# WeatherStation_pcb.net
KiCad netlist of a schematic drawn in EAGLE
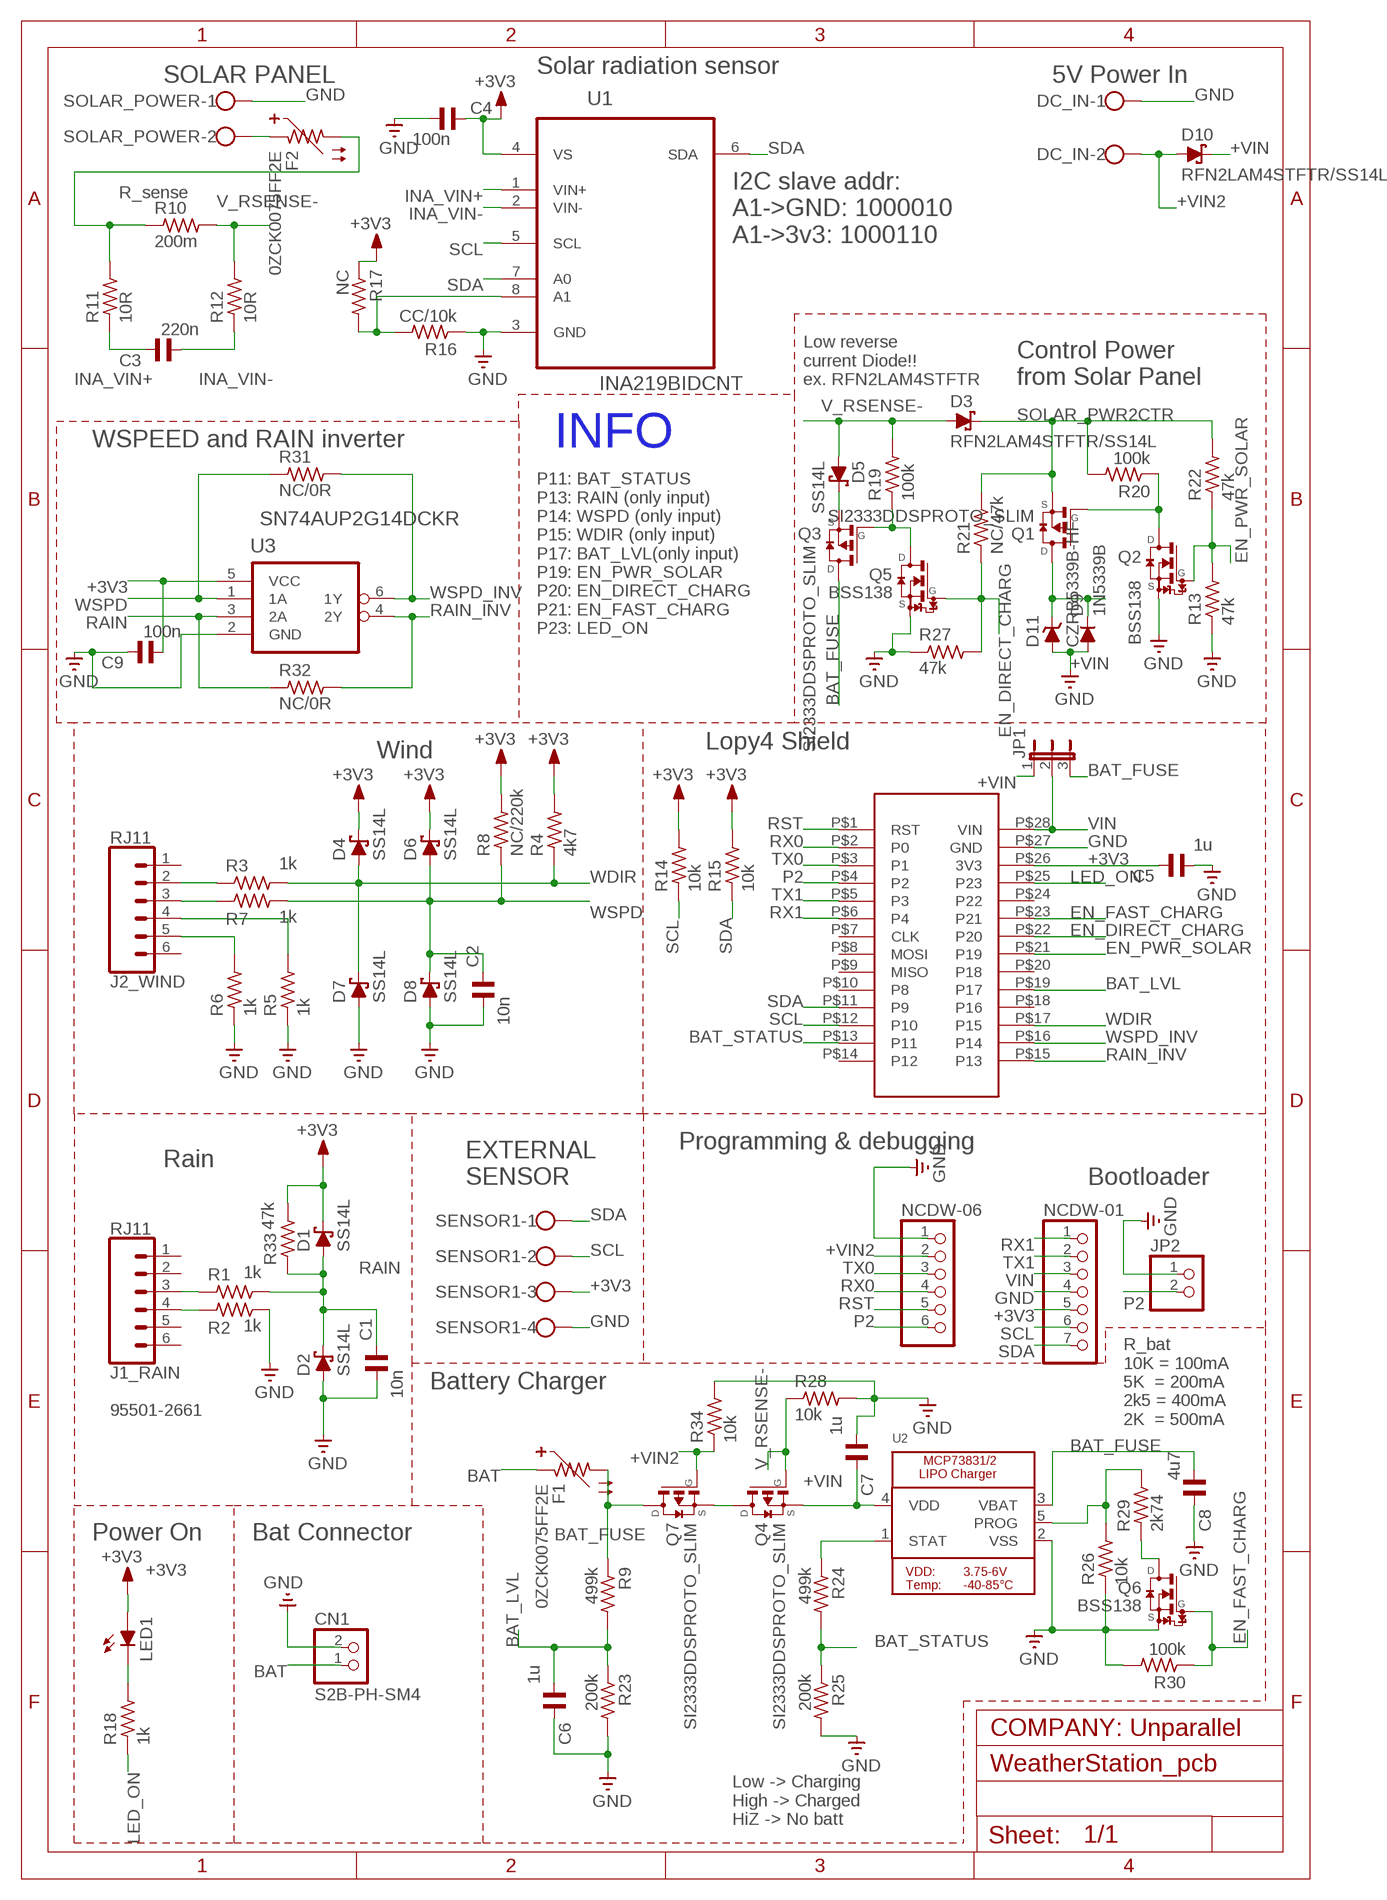
[diagram p0: schematic, sheet 1]

(export (version "E")
  (design (tool "Eeschema 10.0.6"))
  (components
    (comp (ref "C1")
      (value "10n")
      (footprint "eagle-import:C0603_C0805_PROTO_SLIM")
      (libsource (lib "eagle-import") (part "C-EUC0603/C0805_PROTO_SLIM"))
    )
    (comp (ref "C2")
      (value "10n")
      (footprint "eagle-import:C0603_C0805_PROTO_SLIM")
      (libsource (lib "eagle-import") (part "C-EUC0603/C0805_PROTO_SLIM"))
    )
    (comp (ref "C3")
      (value "220n")
      (footprint "eagle-import:C0603")
      (libsource (lib "eagle-import") (part "C-EUC0603"))
    )
    (comp (ref "C4")
      (value "100n")
      (footprint "eagle-import:C0603")
      (libsource (lib "eagle-import") (part "C-EUC0603"))
    )
    (comp (ref "C5")
      (value "1u")
      (footprint "eagle-import:C0603_C0805_PROTO_SLIM")
      (libsource (lib "eagle-import") (part "C-EUC0603/C0805_PROTO_SLIM"))
    )
    (comp (ref "C6")
      (value "1u")
      (footprint "eagle-import:C0603_C0805_PROTO_SLIM")
      (libsource (lib "eagle-import") (part "C-EUC0603/C0805_PROTO_SLIM"))
    )
    (comp (ref "C7")
      (value "1u")
      (footprint "eagle-import:C0603_C0805_PROTO_SLIM")
      (libsource (lib "eagle-import") (part "C-EUC0603/C0805_PROTO_SLIM"))
    )
    (comp (ref "C8")
      (value "4u7")
      (footprint "eagle-import:C0603_C0805_PROTO_SLIM")
      (libsource (lib "eagle-import") (part "C-EUC0603/C0805_PROTO_SLIM"))
    )
    (comp (ref "C9")
      (value "100n")
      (footprint "eagle-import:C0603")
      (libsource (lib "eagle-import") (part "C-EUC0603"))
    )
    (comp (ref "CN1")
      (value "S2B-PH-SM4")
      (footprint "eagle-import:JST-PH-2-SMT-RA")
      (libsource (lib "eagle-import") (part "JST_2PIN-SMT-RA"))
    )
    (comp (ref "D1")
      (value "SS14L")
      (footprint "eagle-import:SUB_SMA_PROTO")
      (libsource (lib "eagle-import") (part "SCHOTTKY-DIODESUB_SMA_PROTO"))
    )
    (comp (ref "D2")
      (value "SS14L")
      (footprint "eagle-import:SUB_SMA_PROTO")
      (libsource (lib "eagle-import") (part "SCHOTTKY-DIODESUB_SMA_PROTO"))
    )
    (comp (ref "D3")
      (value "RFN2LAM4STFTR/SS14L")
      (footprint "eagle-import:SMA_SOD-128_PROTO")
      (libsource (lib "eagle-import") (part "SCHOTTKY-DIODESMA_SOD-128_PROTO"))
    )
    (comp (ref "D4")
      (value "SS14L")
      (footprint "eagle-import:SUB_SMA_PROTO")
      (libsource (lib "eagle-import") (part "SCHOTTKY-DIODESUB_SMA_PROTO"))
    )
    (comp (ref "D5")
      (value "SS14L")
      (footprint "eagle-import:SUB_SMA_PROTO")
      (libsource (lib "eagle-import") (part "SCHOTTKY-DIODESUB_SMA_PROTO"))
    )
    (comp (ref "D6")
      (value "SS14L")
      (footprint "eagle-import:SUB_SMA_PROTO")
      (libsource (lib "eagle-import") (part "SCHOTTKY-DIODESUB_SMA_PROTO"))
    )
    (comp (ref "D7")
      (value "SS14L")
      (footprint "eagle-import:SUB_SMA_PROTO")
      (libsource (lib "eagle-import") (part "SCHOTTKY-DIODESUB_SMA_PROTO"))
    )
    (comp (ref "D8")
      (value "SS14L")
      (footprint "eagle-import:SUB_SMA_PROTO")
      (libsource (lib "eagle-import") (part "SCHOTTKY-DIODESUB_SMA_PROTO"))
    )
    (comp (ref "D9")
      (value "1N5339B")
      (footprint "eagle-import:DO15-12")
      (libsource (lib "eagle-import") (part "DIODE-DO15-12"))
    )
    (comp (ref "D10")
      (value "RFN2LAM4STFTR/SS14L")
      (footprint "eagle-import:SMA_SOD-128_PROTO")
      (libsource (lib "eagle-import") (part "SCHOTTKY-DIODESMA_SOD-128_PROTO"))
    )
    (comp (ref "D11")
      (value "CZRB5339B-HF")
      (footprint "eagle-import:SMB_PROTO")
      (libsource (lib "eagle-import") (part "ZENER-DIODE-PROTO"))
    )
    (comp (ref "DC_IN")
      (value "W237-102")
      (footprint "eagle-import:W237-102")
      (libsource (lib "eagle-import") (part "W237-102"))
    )
    (comp (ref "F1")
      (value "0ZCK0075FF2E")
      (footprint "eagle-import:R0603_R0805_PROTO_SLIM")
      (libsource (lib "eagle-import") (part "PTC-0603_0805_PROTO_SLIM"))
    )
    (comp (ref "F2")
      (value "0ZCK0075FF2E")
      (footprint "eagle-import:R0805")
      (libsource (lib "eagle-import") (part "PTC-0805"))
    )
    (comp (ref "J1_RAIN")
      (value "RJ11")
      (footprint "eagle-import:RJ11-6")
      (libsource (lib "eagle-import") (part "RJ11-6"))
    )
    (comp (ref "J2_WIND")
      (value "RJ11")
      (footprint "eagle-import:RJ11-6")
      (libsource (lib "eagle-import") (part "RJ11-6"))
    )
    (comp (ref "JP1")
      (value "JP2E-0805")
      (footprint "eagle-import:R0805_2")
      (libsource (lib "eagle-import") (part "JP2E-0805"))
    )
    (comp (ref "JP2")
      (value "PINHD-1X2")
      (footprint "eagle-import:1X02")
      (libsource (lib "eagle-import") (part "PINHD-1X2"))
    )
    (comp (ref "LED1")
      (value "LEDCHIP-LED0805")
      (footprint "eagle-import:CHIP-LED0805")
      (libsource (lib "eagle-import") (part "LEDCHIP-LED0805"))
    )
    (comp (ref "NCDW-01")
      (value "PINHD-1X7")
      (footprint "eagle-import:1X07")
      (libsource (lib "eagle-import") (part "PINHD-1X7"))
    )
    (comp (ref "NCDW-06")
      (value "PINHD-1X6")
      (footprint "eagle-import:1X06")
      (libsource (lib "eagle-import") (part "PINHD-1X6"))
    )
    (comp (ref "Q1")
      (value "SI2333DDSPROTO_SLIM")
      (footprint "eagle-import:SOT23_PROTO_SLIM")
      (libsource (lib "eagle-import") (part "SI2333DDSPROTO_SLIM"))
    )
    (comp (ref "Q2")
      (value "BSS138")
      (footprint "eagle-import:SOT23_PROTO_SLIM")
      (libsource (lib "eagle-import") (part "NX7002AKPROTO_SLIM"))
    )
    (comp (ref "Q3")
      (value "SI2333DDSPROTO_SLIM")
      (footprint "eagle-import:SOT23_PROTO_SLIM")
      (libsource (lib "eagle-import") (part "SI2333DDSPROTO_SLIM"))
    )
    (comp (ref "Q4")
      (value "SI2333DDSPROTO_SLIM")
      (footprint "eagle-import:SOT23_PROTO_SLIM")
      (libsource (lib "eagle-import") (part "SI2333DDSPROTO_SLIM"))
    )
    (comp (ref "Q5")
      (value "BSS138")
      (footprint "eagle-import:SOT23_PROTO_SLIM")
      (libsource (lib "eagle-import") (part "NX7002AKPROTO_SLIM"))
    )
    (comp (ref "Q6")
      (value "BSS138")
      (footprint "eagle-import:SOT23_PROTO_SLIM")
      (libsource (lib "eagle-import") (part "NX7002AKPROTO_SLIM"))
    )
    (comp (ref "Q7")
      (value "SI2333DDSPROTO_SLIM")
      (footprint "eagle-import:SOT23_PROTO_SLIM")
      (libsource (lib "eagle-import") (part "SI2333DDSPROTO_SLIM"))
    )
    (comp (ref "R1")
      (value "1k")
      (footprint "eagle-import:R0603")
      (libsource (lib "eagle-import") (part "R-EU_R0603"))
    )
    (comp (ref "R2")
      (value "1k")
      (footprint "eagle-import:R0603")
      (libsource (lib "eagle-import") (part "R-EU_R0603"))
    )
    (comp (ref "R3")
      (value "1k")
      (footprint "eagle-import:R0603")
      (libsource (lib "eagle-import") (part "R-EU_R0603"))
    )
    (comp (ref "R4")
      (value "4k7")
      (footprint "eagle-import:R0603_R0805_PROTO_SLIM")
      (libsource (lib "eagle-import") (part "R-EU_R0603/R0805_PROTO_SLIM"))
    )
    (comp (ref "R5")
      (value "1k")
      (footprint "eagle-import:R0603")
      (libsource (lib "eagle-import") (part "R-EU_R0603"))
    )
    (comp (ref "R6")
      (value "1k")
      (footprint "eagle-import:R0603")
      (libsource (lib "eagle-import") (part "R-EU_R0603"))
    )
    (comp (ref "R7")
      (value "1k")
      (footprint "eagle-import:R0603")
      (libsource (lib "eagle-import") (part "R-EU_R0603"))
    )
    (comp (ref "R8")
      (value "NC/220k")
      (footprint "eagle-import:R0603_R0805_PROTO_SLIM")
      (libsource (lib "eagle-import") (part "R-EU_R0603/R0805_PROTO_SLIM"))
    )
    (comp (ref "R9")
      (value "499k")
      (footprint "eagle-import:R0603_R0805_PROTO_SLIM")
      (libsource (lib "eagle-import") (part "R-EU_R0603/R0805_PROTO_SLIM"))
    )
    (comp (ref "R10")
      (value "200m")
      (footprint "eagle-import:R0603_R0805_PROTO_SLIM")
      (libsource (lib "eagle-import") (part "R-EU_R0603/R0805_PROTO_SLIM"))
    )
    (comp (ref "R11")
      (value "10R")
      (footprint "eagle-import:R0603")
      (libsource (lib "eagle-import") (part "R-EU_R0603"))
    )
    (comp (ref "R12")
      (value "10R")
      (footprint "eagle-import:R0603")
      (libsource (lib "eagle-import") (part "R-EU_R0603"))
    )
    (comp (ref "R13")
      (value "47k")
      (footprint "eagle-import:R0603")
      (libsource (lib "eagle-import") (part "R-EU_R0603"))
    )
    (comp (ref "R14")
      (value "10k")
      (footprint "eagle-import:R0603")
      (libsource (lib "eagle-import") (part "R-EU_R0603"))
    )
    (comp (ref "R15")
      (value "10k")
      (footprint "eagle-import:R0603")
      (libsource (lib "eagle-import") (part "R-EU_R0603"))
    )
    (comp (ref "R16")
      (value "CC/10k")
      (footprint "eagle-import:R0603")
      (libsource (lib "eagle-import") (part "R-EU_R0603"))
    )
    (comp (ref "R17")
      (value "NC")
      (footprint "eagle-import:R0603")
      (libsource (lib "eagle-import") (part "R-EU_R0603"))
    )
    (comp (ref "R18")
      (value "1k")
      (footprint "eagle-import:R0603")
      (libsource (lib "eagle-import") (part "R-EU_R0603"))
    )
    (comp (ref "R19")
      (value "100k")
      (footprint "eagle-import:R0603")
      (libsource (lib "eagle-import") (part "R-EU_R0603"))
    )
    (comp (ref "R20")
      (value "100k")
      (footprint "eagle-import:R0603")
      (libsource (lib "eagle-import") (part "R-EU_R0603"))
    )
    (comp (ref "R21")
      (value "NC/47k")
      (footprint "eagle-import:R0603")
      (libsource (lib "eagle-import") (part "R-EU_R0603"))
    )
    (comp (ref "R22")
      (value "47k")
      (footprint "eagle-import:R0603")
      (libsource (lib "eagle-import") (part "R-EU_R0603"))
    )
    (comp (ref "R23")
      (value "200k")
      (footprint "eagle-import:R0603_R0805_PROTO_SLIM")
      (libsource (lib "eagle-import") (part "R-EU_R0603/R0805_PROTO_SLIM"))
    )
    (comp (ref "R24")
      (value "499k")
      (footprint "eagle-import:R0603_R0805_PROTO_SLIM")
      (libsource (lib "eagle-import") (part "R-EU_R0603/R0805_PROTO_SLIM"))
    )
    (comp (ref "R25")
      (value "200k")
      (footprint "eagle-import:R0603_R0805_PROTO_SLIM")
      (libsource (lib "eagle-import") (part "R-EU_R0603/R0805_PROTO_SLIM"))
    )
    (comp (ref "R26")
      (value "10k")
      (footprint "eagle-import:R0603_R0805_PROTO_SLIM")
      (libsource (lib "eagle-import") (part "R-EU_R0603/R0805_PROTO_SLIM"))
    )
    (comp (ref "R27")
      (value "47k")
      (footprint "eagle-import:R0603")
      (libsource (lib "eagle-import") (part "R-EU_R0603"))
    )
    (comp (ref "R28")
      (value "10k")
      (footprint "eagle-import:R0603")
      (libsource (lib "eagle-import") (part "R-EU_R0603"))
    )
    (comp (ref "R29")
      (value "2k74")
      (footprint "eagle-import:R0603_R0805_PROTO_SLIM")
      (libsource (lib "eagle-import") (part "R-EU_R0603/R0805_PROTO_SLIM"))
    )
    (comp (ref "R30")
      (value "100k")
      (footprint "eagle-import:R0603_R0805_PROTO_SLIM")
      (libsource (lib "eagle-import") (part "R-EU_R0603/R0805_PROTO_SLIM"))
    )
    (comp (ref "R31")
      (value "NC/0R")
      (footprint "eagle-import:R0603_R0805_PROTO_SLIM")
      (libsource (lib "eagle-import") (part "R-EU_R0603/R0805_PROTO_SLIM"))
    )
    (comp (ref "R32")
      (value "NC/0R")
      (footprint "eagle-import:R0603_R0805_PROTO_SLIM")
      (libsource (lib "eagle-import") (part "R-EU_R0603/R0805_PROTO_SLIM"))
    )
    (comp (ref "R33")
      (value "47k")
      (footprint "eagle-import:R0603")
      (libsource (lib "eagle-import") (part "R-EU_R0603"))
    )
    (comp (ref "R34")
      (value "10k")
      (footprint "eagle-import:R0603")
      (libsource (lib "eagle-import") (part "R-EU_R0603"))
    )
    (comp (ref "SENSOR1")
      (value "W237-4")
      (footprint "eagle-import:W237-4")
      (libsource (lib "eagle-import") (part "W237-4"))
    )
    (comp (ref "SOLAR_POWER")
      (value "W237-102")
      (footprint "eagle-import:W237-102")
      (libsource (lib "eagle-import") (part "W237-102"))
    )
    (comp (ref "U$2")
      (value "LOPY4_SHIELD")
      (footprint "eagle-import:LOPY4_SHIELD")
      (libsource (lib "eagle-import") (part "LOPY4_SHIELD"))
    )
    (comp (ref "U1")
      (value "INA219BIDCNT")
      (footprint "eagle-import:SOT65P280X145-8N")
      (libsource (lib "eagle-import") (part "INA219BIDCNT"))
    )
    (comp (ref "U2")
      (value "MCP73831/2")
      (footprint "eagle-import:SOT23-5")
      (libsource (lib "eagle-import") (part "MCP73831/2"))
    )
    (comp (ref "U3")
      (value "SN74AUP2G14DCKR")
      (footprint "eagle-import:SOT65P210X110-6N_EDIT")
      (libsource (lib "eagle-import") (part "SN74AUP2G14-DCKR"))
    )
  )
  (nets
    (net (code "1") (name "+3V3") (class "Default")
      (node (ref "C4") (pin "1") (pinfunction "1_1") (pintype "passive"))
      (node (ref "C5") (pin "1") (pinfunction "1_1") (pintype "passive"))
      (node (ref "C9") (pin "2") (pinfunction "2_2") (pintype "passive"))
      (node (ref "D1") (pin "C") (pinfunction "C_C") (pintype "passive"))
      (node (ref "D4") (pin "C") (pinfunction "C_C") (pintype "passive"))
      (node (ref "D6") (pin "C") (pinfunction "C_C") (pintype "passive"))
      (node (ref "LED1") (pin "A") (pinfunction "A_A") (pintype "passive"))
      (node (ref "NCDW-01") (pin "5") (pinfunction "5_5") (pintype "passive"))
      (node (ref "R14") (pin "2") (pinfunction "2_2") (pintype "passive"))
      (node (ref "R15") (pin "2") (pinfunction "2_2") (pintype "passive"))
      (node (ref "R17") (pin "1") (pinfunction "1_1") (pintype "passive"))
      (node (ref "R33") (pin "2") (pinfunction "2_2") (pintype "passive"))
      (node (ref "R4") (pin "2") (pinfunction "2_2") (pintype "passive"))
      (node (ref "R8") (pin "2") (pinfunction "2_2") (pintype "passive"))
      (node (ref "SENSOR1") (pin "3") (pinfunction "KL_3") (pintype "passive"))
      (node (ref "U$2") (pin "P$26") (pinfunction "3V3_P$26") (pintype "power_in"))
      (node (ref "U1") (pin "4") (pinfunction "VS_4") (pintype "power_in"))
      (node (ref "U3") (pin "5") (pinfunction "VCC_5") (pintype "power_in"))
    )
    (net (code "2") (name "/+VIN") (class "Default")
      (node (ref "C7") (pin "1") (pinfunction "1_1") (pintype "passive"))
      (node (ref "D10") (pin "C") (pinfunction "C_C") (pintype "passive"))
      (node (ref "D11") (pin "C") (pinfunction "C_C") (pintype "passive"))
      (node (ref "D9") (pin "C") (pinfunction "C_C") (pintype "passive"))
      (node (ref "JP1") (pin "1") (pinfunction "1_1") (pintype "passive"))
      (node (ref "Q1") (pin "3") (pinfunction "D_3") (pintype "passive"))
      (node (ref "Q4") (pin "2") (pinfunction "S_2") (pintype "passive"))
      (node (ref "U2") (pin "4") (pinfunction "VDD_4") (pintype "power_in"))
    )
    (net (code "3") (name "/+VIN2") (class "Default")
      (node (ref "D10") (pin "A") (pinfunction "A_A") (pintype "passive"))
      (node (ref "DC_IN") (pin "2") (pinfunction "KL_2") (pintype "passive"))
      (node (ref "NCDW-06") (pin "2") (pinfunction "2_2") (pintype "passive"))
      (node (ref "Q7") (pin "1") (pinfunction "G_1") (pintype "passive"))
      (node (ref "R34") (pin "1") (pinfunction "1_1") (pintype "passive"))
    )
    (net (code "4") (name "/BAT") (class "Default")
      (node (ref "CN1") (pin "1") (pinfunction "2_1") (pintype "passive"))
      (node (ref "F1") (pin "1") (pinfunction "1_1") (pintype "passive"))
    )
    (net (code "5") (name "/BAT_FUSE") (class "Default")
      (node (ref "C8") (pin "2") (pinfunction "2_2") (pintype "passive"))
      (node (ref "F1") (pin "2") (pinfunction "2_2") (pintype "passive"))
      (node (ref "JP1") (pin "3") (pinfunction "3_3") (pintype "passive"))
      (node (ref "Q3") (pin "3") (pinfunction "D_3") (pintype "passive"))
      (node (ref "Q7") (pin "3") (pinfunction "D_3") (pintype "passive"))
      (node (ref "R9") (pin "1") (pinfunction "1_1") (pintype "passive"))
      (node (ref "U2") (pin "3") (pinfunction "VBAT_3") (pintype "power_in"))
    )
    (net (code "6") (name "/BAT_LVL") (class "Default")
      (node (ref "C6") (pin "2") (pinfunction "2_2") (pintype "passive"))
      (node (ref "R23") (pin "1") (pinfunction "1_1") (pintype "passive"))
      (node (ref "R9") (pin "2") (pinfunction "2_2") (pintype "passive"))
      (node (ref "U$2") (pin "P$19") (pinfunction "P17_P$19") (pintype "bidirectional"))
    )
    (net (code "7") (name "/BAT_STATUS") (class "Default")
      (node (ref "R24") (pin "2") (pinfunction "2_2") (pintype "passive"))
      (node (ref "R25") (pin "1") (pinfunction "1_1") (pintype "passive"))
      (node (ref "U$2") (pin "P$13") (pinfunction "P11_P$13") (pintype "bidirectional"))
    )
    (net (code "8") (name "/EN_DIRECT_CHARG") (class "Default")
      (node (ref "Q5") (pin "1") (pinfunction "G_1") (pintype "passive"))
      (node (ref "R21") (pin "1") (pinfunction "1_1") (pintype "passive"))
      (node (ref "R27") (pin "2") (pinfunction "2_2") (pintype "passive"))
      (node (ref "U$2") (pin "P$22") (pinfunction "P20_P$22") (pintype "bidirectional"))
    )
    (net (code "9") (name "/EN_FAST_CHARG") (class "Default")
      (node (ref "Q6") (pin "1") (pinfunction "G_1") (pintype "passive"))
      (node (ref "R30") (pin "1") (pinfunction "1_1") (pintype "passive"))
      (node (ref "U$2") (pin "P$23") (pinfunction "P21_P$23") (pintype "bidirectional"))
    )
    (net (code "10") (name "/EN_PWR_SOLAR") (class "Default")
      (node (ref "Q2") (pin "1") (pinfunction "G_1") (pintype "passive"))
      (node (ref "R13") (pin "2") (pinfunction "2_2") (pintype "passive"))
      (node (ref "R22") (pin "1") (pinfunction "1_1") (pintype "passive"))
      (node (ref "U$2") (pin "P$21") (pinfunction "P19_P$21") (pintype "bidirectional"))
    )
    (net (code "11") (name "/INA_VIN+") (class "Default")
      (node (ref "C3") (pin "1") (pinfunction "1_1") (pintype "passive"))
      (node (ref "R11") (pin "1") (pinfunction "1_1") (pintype "passive"))
      (node (ref "U1") (pin "1") (pinfunction "VIN+_1") (pintype "power_in"))
    )
    (net (code "12") (name "/INA_VIN-") (class "Default")
      (node (ref "C3") (pin "2") (pinfunction "2_2") (pintype "passive"))
      (node (ref "R12") (pin "1") (pinfunction "1_1") (pintype "passive"))
      (node (ref "U1") (pin "2") (pinfunction "VIN-_2") (pintype "power_in"))
    )
    (net (code "13") (name "/LED_ON") (class "Default")
      (node (ref "R18") (pin "1") (pinfunction "1_1") (pintype "passive"))
      (node (ref "U$2") (pin "P$25") (pinfunction "P23_P$25") (pintype "bidirectional"))
    )
    (net (code "14") (name "/P2") (class "Default")
      (node (ref "JP2") (pin "2") (pinfunction "2_2") (pintype "passive"))
      (node (ref "NCDW-06") (pin "6") (pinfunction "6_6") (pintype "passive"))
      (node (ref "U$2") (pin "P$4") (pinfunction "P2_P$4") (pintype "bidirectional"))
    )
    (net (code "15") (name "/RAIN") (class "Default")
      (node (ref "C1") (pin "1") (pinfunction "1_1") (pintype "passive"))
      (node (ref "D1") (pin "A") (pinfunction "A_A") (pintype "passive"))
      (node (ref "D2") (pin "C") (pinfunction "C_C") (pintype "passive"))
      (node (ref "R1") (pin "2") (pinfunction "2_2") (pintype "passive"))
      (node (ref "R32") (pin "1") (pinfunction "1_1") (pintype "passive"))
      (node (ref "R33") (pin "1") (pinfunction "1_1") (pintype "passive"))
      (node (ref "U3") (pin "3") (pinfunction "2A_3") (pintype "input"))
    )
    (net (code "16") (name "/RAIN_INV") (class "Default")
      (node (ref "R32") (pin "2") (pinfunction "2_2") (pintype "passive"))
      (node (ref "U$2") (pin "P$15") (pinfunction "P13_P$15") (pintype "bidirectional"))
      (node (ref "U3") (pin "4") (pinfunction "2Y_4") (pintype "output"))
    )
    (net (code "17") (name "/RST") (class "Default")
      (node (ref "NCDW-06") (pin "5") (pinfunction "5_5") (pintype "passive"))
      (node (ref "U$2") (pin "P$1") (pinfunction "RST_P$1") (pintype "input"))
    )
    (net (code "18") (name "/RX0") (class "Default")
      (node (ref "NCDW-06") (pin "4") (pinfunction "4_4") (pintype "passive"))
      (node (ref "U$2") (pin "P$2") (pinfunction "P0_P$2") (pintype "bidirectional"))
    )
    (net (code "19") (name "/RX1") (class "Default")
      (node (ref "NCDW-01") (pin "1") (pinfunction "1_1") (pintype "passive"))
      (node (ref "U$2") (pin "P$6") (pinfunction "P4_P$6") (pintype "bidirectional"))
    )
    (net (code "20") (name "/SCL") (class "Default")
      (node (ref "NCDW-01") (pin "6") (pinfunction "6_6") (pintype "passive"))
      (node (ref "R14") (pin "1") (pinfunction "1_1") (pintype "passive"))
      (node (ref "SENSOR1") (pin "2") (pinfunction "KL_2") (pintype "passive"))
      (node (ref "U$2") (pin "P$12") (pinfunction "P10_P$12") (pintype "bidirectional"))
      (node (ref "U1") (pin "5") (pinfunction "SCL_5") (pintype "input"))
    )
    (net (code "21") (name "/SDA") (class "Default")
      (node (ref "NCDW-01") (pin "7") (pinfunction "7_7") (pintype "passive"))
      (node (ref "R15") (pin "1") (pinfunction "1_1") (pintype "passive"))
      (node (ref "SENSOR1") (pin "1") (pinfunction "KL_1") (pintype "passive"))
      (node (ref "U$2") (pin "P$11") (pinfunction "P9_P$11") (pintype "bidirectional"))
      (node (ref "U1") (pin "6") (pinfunction "SDA_6") (pintype "bidirectional"))
      (node (ref "U1") (pin "7") (pinfunction "A0_7") (pintype "input"))
    )
    (net (code "22") (name "/SOLAR_PWR2CTR") (class "Default")
      (node (ref "D3") (pin "C") (pinfunction "C_C") (pintype "passive"))
      (node (ref "Q1") (pin "2") (pinfunction "S_2") (pintype "passive"))
      (node (ref "R20") (pin "2") (pinfunction "2_2") (pintype "passive"))
      (node (ref "R21") (pin "2") (pinfunction "2_2") (pintype "passive"))
      (node (ref "R22") (pin "2") (pinfunction "2_2") (pintype "passive"))
    )
    (net (code "23") (name "/TX0") (class "Default")
      (node (ref "NCDW-06") (pin "3") (pinfunction "3_3") (pintype "passive"))
      (node (ref "U$2") (pin "P$3") (pinfunction "P1_P$3") (pintype "bidirectional"))
    )
    (net (code "24") (name "/TX1") (class "Default")
      (node (ref "NCDW-01") (pin "2") (pinfunction "2_2") (pintype "passive"))
      (node (ref "U$2") (pin "P$5") (pinfunction "P3_P$5") (pintype "bidirectional"))
    )
    (net (code "25") (name "/VIN") (class "Default")
      (node (ref "JP1") (pin "2") (pinfunction "2_2") (pintype "passive"))
      (node (ref "NCDW-01") (pin "3") (pinfunction "3_3") (pintype "passive"))
      (node (ref "U$2") (pin "P$28") (pinfunction "VIN_P$28") (pintype "power_in"))
    )
    (net (code "26") (name "/V_RSENSE-") (class "Default")
      (node (ref "D3") (pin "A") (pinfunction "A_A") (pintype "passive"))
      (node (ref "D5") (pin "A") (pinfunction "A_A") (pintype "passive"))
      (node (ref "Q4") (pin "1") (pinfunction "G_1") (pintype "passive"))
      (node (ref "R10") (pin "2") (pinfunction "2_2") (pintype "passive"))
      (node (ref "R12") (pin "2") (pinfunction "2_2") (pintype "passive"))
      (node (ref "R19") (pin "2") (pinfunction "2_2") (pintype "passive"))
      (node (ref "R28") (pin "1") (pinfunction "1_1") (pintype "passive"))
    )
    (net (code "27") (name "/WDIR") (class "Default")
      (node (ref "D4") (pin "A") (pinfunction "A_A") (pintype "passive"))
      (node (ref "D7") (pin "C") (pinfunction "C_C") (pintype "passive"))
      (node (ref "R3") (pin "2") (pinfunction "2_2") (pintype "passive"))
      (node (ref "R4") (pin "1") (pinfunction "1_1") (pintype "passive"))
      (node (ref "U$2") (pin "P$17") (pinfunction "P15_P$17") (pintype "bidirectional"))
    )
    (net (code "28") (name "/WSPD") (class "Default")
      (node (ref "C2") (pin "1") (pinfunction "1_1") (pintype "passive"))
      (node (ref "D6") (pin "A") (pinfunction "A_A") (pintype "passive"))
      (node (ref "D8") (pin "C") (pinfunction "C_C") (pintype "passive"))
      (node (ref "R31") (pin "1") (pinfunction "1_1") (pintype "passive"))
      (node (ref "R7") (pin "2") (pinfunction "2_2") (pintype "passive"))
      (node (ref "R8") (pin "1") (pinfunction "1_1") (pintype "passive"))
      (node (ref "U3") (pin "1") (pinfunction "1A_1") (pintype "input"))
    )
    (net (code "29") (name "/WSPD_INV") (class "Default")
      (node (ref "R31") (pin "2") (pinfunction "2_2") (pintype "passive"))
      (node (ref "U$2") (pin "P$16") (pinfunction "P14_P$16") (pintype "bidirectional"))
      (node (ref "U3") (pin "6") (pinfunction "1Y_6") (pintype "output"))
    )
    (net (code "30") (name "GND") (class "Default")
      (node (ref "C1") (pin "2") (pinfunction "2_2") (pintype "passive"))
      (node (ref "C2") (pin "2") (pinfunction "2_2") (pintype "passive"))
      (node (ref "C4") (pin "2") (pinfunction "2_2") (pintype "passive"))
      (node (ref "C5") (pin "2") (pinfunction "2_2") (pintype "passive"))
      (node (ref "C6") (pin "1") (pinfunction "1_1") (pintype "passive"))
      (node (ref "C7") (pin "2") (pinfunction "2_2") (pintype "passive"))
      (node (ref "C8") (pin "1") (pinfunction "1_1") (pintype "passive"))
      (node (ref "C9") (pin "1") (pinfunction "1_1") (pintype "passive"))
      (node (ref "CN1") (pin "2") (pinfunction "1_2") (pintype "passive"))
      (node (ref "D11") (pin "A") (pinfunction "A_A") (pintype "passive"))
      (node (ref "D2") (pin "A") (pinfunction "A_A") (pintype "passive"))
      (node (ref "D7") (pin "A") (pinfunction "A_A") (pintype "passive"))
      (node (ref "D8") (pin "A") (pinfunction "A_A") (pintype "passive"))
      (node (ref "D9") (pin "A") (pinfunction "A_A") (pintype "passive"))
      (node (ref "DC_IN") (pin "1") (pinfunction "KL_1") (pintype "passive"))
      (node (ref "JP2") (pin "1") (pinfunction "1_1") (pintype "passive"))
      (node (ref "NCDW-01") (pin "4") (pinfunction "4_4") (pintype "passive"))
      (node (ref "NCDW-06") (pin "1") (pinfunction "1_1") (pintype "passive"))
      (node (ref "Q2") (pin "2") (pinfunction "S_2") (pintype "passive"))
      (node (ref "Q5") (pin "2") (pinfunction "S_2") (pintype "passive"))
      (node (ref "Q6") (pin "2") (pinfunction "S_2") (pintype "passive"))
      (node (ref "R13") (pin "1") (pinfunction "1_1") (pintype "passive"))
      (node (ref "R16") (pin "1") (pinfunction "1_1") (pintype "passive"))
      (node (ref "R2") (pin "2") (pinfunction "2_2") (pintype "passive"))
      (node (ref "R23") (pin "2") (pinfunction "2_2") (pintype "passive"))
      (node (ref "R25") (pin "2") (pinfunction "2_2") (pintype "passive"))
      (node (ref "R26") (pin "1") (pinfunction "1_1") (pintype "passive"))
      (node (ref "R27") (pin "1") (pinfunction "1_1") (pintype "passive"))
      (node (ref "R28") (pin "2") (pinfunction "2_2") (pintype "passive"))
      (node (ref "R30") (pin "2") (pinfunction "2_2") (pintype "passive"))
      (node (ref "R34") (pin "2") (pinfunction "2_2") (pintype "passive"))
      (node (ref "R5") (pin "1") (pinfunction "1_1") (pintype "passive"))
      (node (ref "R6") (pin "1") (pinfunction "1_1") (pintype "passive"))
      (node (ref "SENSOR1") (pin "4") (pinfunction "KL_4") (pintype "passive"))
      (node (ref "SOLAR_POWER") (pin "1") (pinfunction "KL_1") (pintype "passive"))
      (node (ref "U$2") (pin "P$27") (pinfunction "GND_P$27") (pintype "power_in"))
      (node (ref "U1") (pin "3") (pinfunction "GND_3") (pintype "passive"))
      (node (ref "U2") (pin "2") (pinfunction "VSS_2") (pintype "power_in"))
      (node (ref "U3") (pin "2") (pinfunction "GND_2") (pintype "passive"))
    )
    (net (code "31") (name "Net-(F2-Pad2)") (class "Default")
      (node (ref "F2") (pin "2") (pinfunction "2_2") (pintype "passive"))
      (node (ref "R10") (pin "1") (pinfunction "1_1") (pintype "passive"))
      (node (ref "R11") (pin "2") (pinfunction "2_2") (pintype "passive"))
    )
    (net (code "32") (name "Net-(J1_RAIN-Pad3)") (class "Default")
      (node (ref "J1_RAIN") (pin "3") (pinfunction "3_3") (pintype "passive"))
      (node (ref "R1") (pin "1") (pinfunction "1_1") (pintype "passive"))
    )
    (net (code "33") (name "Net-(J1_RAIN-Pad4)") (class "Default")
      (node (ref "J1_RAIN") (pin "4") (pinfunction "4_4") (pintype "passive"))
      (node (ref "R2") (pin "1") (pinfunction "1_1") (pintype "passive"))
    )
    (net (code "34") (name "Net-(J2_WIND-Pad2)") (class "Default")
      (node (ref "J2_WIND") (pin "2") (pinfunction "2_2") (pintype "passive"))
      (node (ref "R3") (pin "1") (pinfunction "1_1") (pintype "passive"))
    )
    (net (code "35") (name "Net-(J2_WIND-Pad3)") (class "Default")
      (node (ref "J2_WIND") (pin "3") (pinfunction "3_3") (pintype "passive"))
      (node (ref "R7") (pin "1") (pinfunction "1_1") (pintype "passive"))
    )
    (net (code "36") (name "Net-(J2_WIND-Pad4)") (class "Default")
      (node (ref "J2_WIND") (pin "4") (pinfunction "4_4") (pintype "passive"))
      (node (ref "R5") (pin "2") (pinfunction "2_2") (pintype "passive"))
    )
    (net (code "37") (name "Net-(J2_WIND-Pad5)") (class "Default")
      (node (ref "J2_WIND") (pin "5") (pinfunction "5_5") (pintype "passive"))
      (node (ref "R6") (pin "2") (pinfunction "2_2") (pintype "passive"))
    )
    (net (code "38") (name "Net-(LED1-PadC)") (class "Default")
      (node (ref "LED1") (pin "C") (pinfunction "C_C") (pintype "passive"))
      (node (ref "R18") (pin "2") (pinfunction "2_2") (pintype "passive"))
    )
    (net (code "39") (name "Net-(Q1-G)") (class "Default")
      (node (ref "Q1") (pin "1") (pinfunction "G_1") (pintype "passive"))
      (node (ref "Q2") (pin "3") (pinfunction "D_3") (pintype "passive"))
      (node (ref "R20") (pin "1") (pinfunction "1_1") (pintype "passive"))
    )
    (net (code "40") (name "Net-(Q3-G)") (class "Default")
      (node (ref "Q3") (pin "1") (pinfunction "G_1") (pintype "passive"))
      (node (ref "Q5") (pin "3") (pinfunction "D_3") (pintype "passive"))
      (node (ref "R19") (pin "1") (pinfunction "1_1") (pintype "passive"))
    )
    (net (code "41") (name "Net-(Q3-S)") (class "Default")
      (node (ref "D5") (pin "C") (pinfunction "C_C") (pintype "passive"))
      (node (ref "Q3") (pin "2") (pinfunction "S_2") (pintype "passive"))
    )
    (net (code "42") (name "Net-(Q4-D)") (class "Default")
      (node (ref "Q4") (pin "3") (pinfunction "D_3") (pintype "passive"))
      (node (ref "Q7") (pin "2") (pinfunction "S_2") (pintype "passive"))
    )
    (net (code "43") (name "Net-(Q6-D)") (class "Default")
      (node (ref "Q6") (pin "3") (pinfunction "D_3") (pintype "passive"))
      (node (ref "R29") (pin "1") (pinfunction "1_1") (pintype "passive"))
    )
    (net (code "44") (name "Net-(SOLAR_POWERB-KL)") (class "Default")
      (node (ref "F2") (pin "1") (pinfunction "1_1") (pintype "passive"))
      (node (ref "SOLAR_POWER") (pin "2") (pinfunction "KL_2") (pintype "passive"))
    )
    (net (code "45") (name "Net-(U1-A1)") (class "Default")
      (node (ref "R16") (pin "2") (pinfunction "2_2") (pintype "passive"))
      (node (ref "R17") (pin "2") (pinfunction "2_2") (pintype "passive"))
      (node (ref "U1") (pin "8") (pinfunction "A1_8") (pintype "input"))
    )
    (net (code "46") (name "Net-(U2-PROG)") (class "Default")
      (node (ref "R26") (pin "2") (pinfunction "2_2") (pintype "passive"))
      (node (ref "R29") (pin "2") (pinfunction "2_2") (pintype "passive"))
      (node (ref "U2") (pin "5") (pinfunction "PROG_5") (pintype "input"))
    )
    (net (code "47") (name "Net-(U2-STAT)") (class "Default")
      (node (ref "R24") (pin "1") (pinfunction "1_1") (pintype "passive"))
      (node (ref "U2") (pin "1") (pinfunction "STAT_1") (pintype "output"))
    )
    (net (code "48") (name "unconnected-(J1_RAIN-Pad1)") (class "Default")
      (node (ref "J1_RAIN") (pin "1") (pinfunction "1_1") (pintype "passive"))
    )
    (net (code "49") (name "unconnected-(J1_RAIN-Pad2)") (class "Default")
      (node (ref "J1_RAIN") (pin "2") (pinfunction "2_2") (pintype "passive"))
    )
    (net (code "50") (name "unconnected-(J1_RAIN-Pad5)") (class "Default")
      (node (ref "J1_RAIN") (pin "5") (pinfunction "5_5") (pintype "passive"))
    )
    (net (code "51") (name "unconnected-(J1_RAIN-Pad6)") (class "Default")
      (node (ref "J1_RAIN") (pin "6") (pinfunction "6_6") (pintype "passive"))
    )
    (net (code "52") (name "unconnected-(J2_WIND-Pad1)") (class "Default")
      (node (ref "J2_WIND") (pin "1") (pinfunction "1_1") (pintype "passive"))
    )
    (net (code "53") (name "unconnected-(J2_WIND-Pad6)") (class "Default")
      (node (ref "J2_WIND") (pin "6") (pinfunction "6_6") (pintype "passive"))
    )
    (net (code "54") (name "unconnected-(U$2-CLK-PadP$7)") (class "Default")
      (node (ref "U$2") (pin "P$7") (pinfunction "CLK_P$7") (pintype "bidirectional"))
    )
    (net (code "55") (name "unconnected-(U$2-MISO-PadP$9)") (class "Default")
      (node (ref "U$2") (pin "P$9") (pinfunction "MISO_P$9") (pintype "bidirectional"))
    )
    (net (code "56") (name "unconnected-(U$2-MOSI-PadP$8)") (class "Default")
      (node (ref "U$2") (pin "P$8") (pinfunction "MOSI_P$8") (pintype "bidirectional"))
    )
    (net (code "57") (name "unconnected-(U$2-P8-PadP$10)") (class "Default")
      (node (ref "U$2") (pin "P$10") (pinfunction "P8_P$10") (pintype "bidirectional"))
    )
    (net (code "58") (name "unconnected-(U$2-P12-PadP$14)") (class "Default")
      (node (ref "U$2") (pin "P$14") (pinfunction "P12_P$14") (pintype "bidirectional"))
    )
    (net (code "59") (name "unconnected-(U$2-P16-PadP$18)") (class "Default")
      (node (ref "U$2") (pin "P$18") (pinfunction "P16_P$18") (pintype "bidirectional"))
    )
    (net (code "60") (name "unconnected-(U$2-P18-PadP$20)") (class "Default")
      (node (ref "U$2") (pin "P$20") (pinfunction "P18_P$20") (pintype "bidirectional"))
    )
    (net (code "61") (name "unconnected-(U$2-P22-PadP$24)") (class "Default")
      (node (ref "U$2") (pin "P$24") (pinfunction "P22_P$24") (pintype "bidirectional"))
    )
  )
)
